# Switch-N-Sense.net
KiCad netlist of a schematic drawn in EAGLE
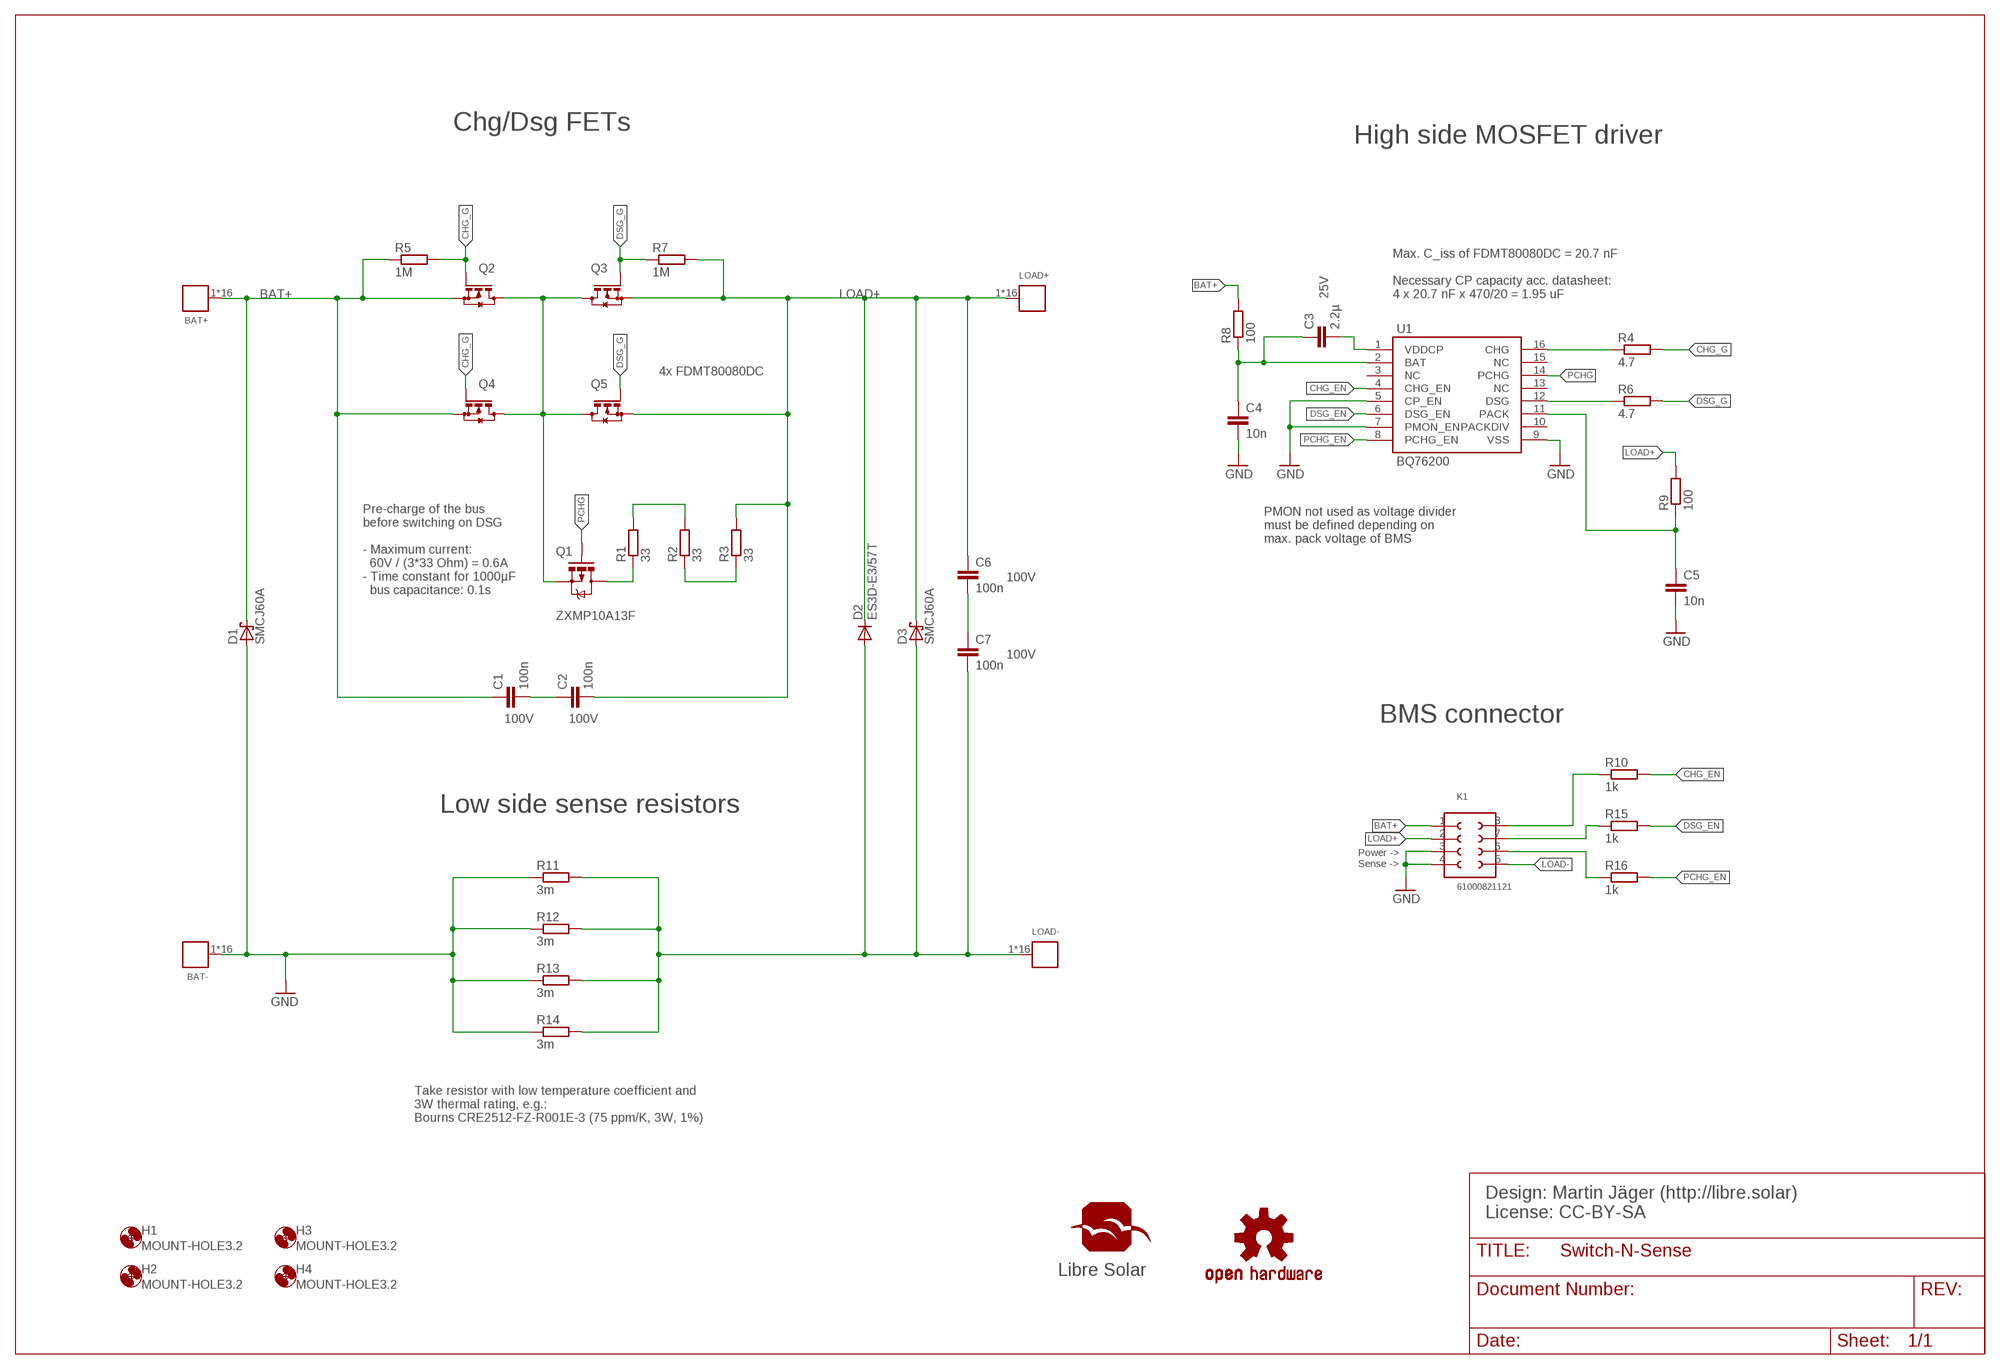
[diagram p0: schematic, sheet 1]

(export (version "E")
  (design (tool "Eeschema 10.0.6"))
  (components
    (comp (ref "BAT+")
      (value "WP-BUCF_G")
      (footprint "eagle-import:16PINS_CIR")
      (libsource (lib "eagle-import") (part "WP-BUCF_G"))
    )
    (comp (ref "BAT-")
      (value "WP-BUCF_G")
      (footprint "eagle-import:16PINS_CIR")
      (libsource (lib "eagle-import") (part "WP-BUCF_G"))
    )
    (comp (ref "C1")
      (value "100n")
      (footprint "eagle-import:C0603")
      (fields (field (name "MF") "WALSIN") (field (name "MPN") "0603B104K500CT"))
      (libsource (lib "eagle-import") (part "C-EUC0603"))
    )
    (comp (ref "C2")
      (value "100n")
      (footprint "eagle-import:C0603")
      (fields (field (name "MF") "WALSIN") (field (name "MPN") "0603B104K500CT"))
      (libsource (lib "eagle-import") (part "C-EUC0603"))
    )
    (comp (ref "C3")
      (value "2.2µ")
      (footprint "eagle-import:C0805")
      (fields (field (name "MF") "WALSIN") (field (name "MPN") "0603B104K500CT"))
      (libsource (lib "eagle-import") (part "C-EUC0805"))
    )
    (comp (ref "C4")
      (value "10n")
      (footprint "eagle-import:C0603")
      (fields (field (name "MF") "MURATA") (field (name "MPN") "GRM188R71H103KA01D."))
      (libsource (lib "eagle-import") (part "C-EUC0603"))
    )
    (comp (ref "C5")
      (value "10n")
      (footprint "eagle-import:C0603")
      (fields (field (name "MF") "MURATA") (field (name "MPN") "GRM188R71H103KA01D."))
      (libsource (lib "eagle-import") (part "C-EUC0603"))
    )
    (comp (ref "C6")
      (value "100n")
      (footprint "eagle-import:C0603")
      (fields (field (name "MF") "WALSIN") (field (name "MPN") "0603B104K500CT"))
      (libsource (lib "eagle-import") (part "C-EUC0603"))
    )
    (comp (ref "C7")
      (value "100n")
      (footprint "eagle-import:C0603")
      (fields (field (name "MF") "WALSIN") (field (name "MPN") "0603B104K500CT"))
      (libsource (lib "eagle-import") (part "C-EUC0603"))
    )
    (comp (ref "D1")
      (value "SMCJ60A")
      (footprint "eagle-import:SMC")
      (fields (field (name "MF") "FAIRCHILD SEMICONDUCTOR") (field (name "MPN") "SMCJ75A"))
      (libsource (lib "eagle-import") (part "SCHOTTKY-DIODESMC"))
    )
    (comp (ref "D2")
      (value "ES3D-E3/57T")
      (footprint "eagle-import:SMC")
      (fields (field (name "MF") "VISHAY") (field (name "MPN") "ES3D-E3/57T."))
      (libsource (lib "eagle-import") (part "DIODE-SMC"))
    )
    (comp (ref "D3")
      (value "SMCJ60A")
      (footprint "eagle-import:SMC")
      (fields (field (name "MF") "FAIRCHILD SEMICONDUCTOR") (field (name "MPN") "SMCJ75A"))
      (libsource (lib "eagle-import") (part "SCHOTTKY-DIODESMC"))
    )
    (comp (ref "H1")
      (value "MOUNT-HOLE3.2")
      (footprint "eagle-import:3,2")
      (libsource (lib "eagle-import") (part "MOUNT-HOLE3.2"))
    )
    (comp (ref "H2")
      (value "MOUNT-HOLE3.2")
      (footprint "eagle-import:3,2")
      (libsource (lib "eagle-import") (part "MOUNT-HOLE3.2"))
    )
    (comp (ref "H3")
      (value "MOUNT-HOLE3.2")
      (footprint "eagle-import:3,2")
      (libsource (lib "eagle-import") (part "MOUNT-HOLE3.2"))
    )
    (comp (ref "H4")
      (value "MOUNT-HOLE3.2")
      (footprint "eagle-import:3,2")
      (libsource (lib "eagle-import") (part "MOUNT-HOLE3.2"))
    )
    (comp (ref "K1")
      (value "61000821121")
      (footprint "eagle-import:61000821121")
      (libsource (lib "eagle-import") (part "61000821121"))
    )
    (comp (ref "LOAD+")
      (value "WP-BUCF_G")
      (footprint "eagle-import:16PINS_CIR")
      (libsource (lib "eagle-import") (part "WP-BUCF_G"))
    )
    (comp (ref "LOAD-")
      (value "WP-BUCF_G")
      (footprint "eagle-import:16PINS_CIR")
      (libsource (lib "eagle-import") (part "WP-BUCF_G"))
    )
    (comp (ref "N1")
      (value "OSHW-LOGOM")
      (footprint "eagle-import:OSHW-LOGO-M")
      (libsource (lib "eagle-import") (part "OSHW-LOGOM"))
    )
    (comp (ref "Q1")
      (value "ZXMP10A13F")
      (footprint "eagle-import:SOT23-3")
      (fields (field (name "MF") "DIODES INC.") (field (name "MPN") "ZXMP10A13FTA"))
      (libsource (lib "eagle-import") (part "MOSFET-PCHANNEL"))
    )
    (comp (ref "Q2")
      (value "FDMT80080DC")
      (footprint "eagle-import:FDMT80080DC")
      (libsource (lib "eagle-import") (part "FDMT80080DC"))
    )
    (comp (ref "Q3")
      (value "FDMT80080DC")
      (footprint "eagle-import:FDMT80080DC")
      (libsource (lib "eagle-import") (part "FDMT80080DC"))
    )
    (comp (ref "Q4")
      (value "FDMT80080DC")
      (footprint "eagle-import:FDMT80080DC")
      (libsource (lib "eagle-import") (part "FDMT80080DC"))
    )
    (comp (ref "Q5")
      (value "FDMT80080DC")
      (footprint "eagle-import:FDMT80080DC")
      (libsource (lib "eagle-import") (part "FDMT80080DC"))
    )
    (comp (ref "R1")
      (value "33")
      (footprint "eagle-import:R2010")
      (fields (field (name "MF") "WELWYN") (field (name "MPN") "ASC2010-33RFT4"))
      (libsource (lib "eagle-import") (part "R-EU_R2010"))
    )
    (comp (ref "R2")
      (value "33")
      (footprint "eagle-import:R2010")
      (fields (field (name "MF") "WELWYN") (field (name "MPN") "ASC2010-33RFT4"))
      (libsource (lib "eagle-import") (part "R-EU_R2010"))
    )
    (comp (ref "R3")
      (value "33")
      (footprint "eagle-import:R2010")
      (fields (field (name "MF") "WELWYN") (field (name "MPN") "ASC2010-33RFT4"))
      (libsource (lib "eagle-import") (part "R-EU_R2010"))
    )
    (comp (ref "R4")
      (value "4.7")
      (footprint "eagle-import:R0603")
      (fields (field (name "MF") "PANASONIC ELECTRONIC COMPONENTS") (field (name "MPN") "ERJU06F1004V"))
      (libsource (lib "eagle-import") (part "R-EU_R0603"))
    )
    (comp (ref "R5")
      (value "1M")
      (footprint "eagle-import:R0603")
      (fields (field (name "MF") "PANASONIC ELECTRONIC COMPONENTS") (field (name "MPN") "ERJU06F1004V"))
      (libsource (lib "eagle-import") (part "R-EU_R0603"))
    )
    (comp (ref "R6")
      (value "4.7")
      (footprint "eagle-import:R0603")
      (fields (field (name "MF") "PANASONIC ELECTRONIC COMPONENTS") (field (name "MPN") "ERJU06F1004V"))
      (libsource (lib "eagle-import") (part "R-EU_R0603"))
    )
    (comp (ref "R7")
      (value "1M")
      (footprint "eagle-import:R0603")
      (fields (field (name "MF") "PANASONIC ELECTRONIC COMPONENTS") (field (name "MPN") "ERJU06F1004V"))
      (libsource (lib "eagle-import") (part "R-EU_R0603"))
    )
    (comp (ref "R8")
      (value "100")
      (footprint "eagle-import:R0603")
      (fields (field (name "MF") "MULTICOMP") (field (name "MPN") "MCMR06X1001FTL"))
      (libsource (lib "eagle-import") (part "R-EU_R0603"))
    )
    (comp (ref "R9")
      (value "100")
      (footprint "eagle-import:R0603")
      (fields (field (name "MF") "MULTICOMP") (field (name "MPN") "MCMR06X1001FTL"))
      (libsource (lib "eagle-import") (part "R-EU_R0603"))
    )
    (comp (ref "R10")
      (value "1k")
      (footprint "eagle-import:R0603")
      (fields (field (name "MF") "PANASONIC ELECTRONIC COMPONENTS") (field (name "MPN") "ERJU06F1004V"))
      (libsource (lib "eagle-import") (part "R-EU_R0603"))
    )
    (comp (ref "R11")
      (value "3m")
      (footprint "eagle-import:R2512")
      (libsource (lib "eagle-import") (part "R-EU_R2512"))
    )
    (comp (ref "R12")
      (value "3m")
      (footprint "eagle-import:R2512")
      (libsource (lib "eagle-import") (part "R-EU_R2512"))
    )
    (comp (ref "R13")
      (value "3m")
      (footprint "eagle-import:R2512")
      (libsource (lib "eagle-import") (part "R-EU_R2512"))
    )
    (comp (ref "R14")
      (value "3m")
      (footprint "eagle-import:R2512")
      (libsource (lib "eagle-import") (part "R-EU_R2512"))
    )
    (comp (ref "R15")
      (value "1k")
      (footprint "eagle-import:R0603")
      (fields (field (name "MF") "PANASONIC ELECTRONIC COMPONENTS") (field (name "MPN") "ERJU06F1004V"))
      (libsource (lib "eagle-import") (part "R-EU_R0603"))
    )
    (comp (ref "R16")
      (value "1k")
      (footprint "eagle-import:R0603")
      (fields (field (name "MF") "PANASONIC ELECTRONIC COMPONENTS") (field (name "MPN") "ERJU06F1004V"))
      (libsource (lib "eagle-import") (part "R-EU_R0603"))
    )
    (comp (ref "U$1")
      (value "LIBRESOLAR_LOGO")
      (footprint "eagle-import:LIBRESOLAR_LOGO")
      (libsource (lib "eagle-import") (part "LIBRESOLAR_LOGO"))
    )
    (comp (ref "U1")
      (value "BQ76200")
      (footprint "eagle-import:TSSOP16")
      (libsource (lib "eagle-import") (part "BQ76200"))
    )
  )
  (nets
    (net (code "1") (name "BAT+") (class "Default")
      (node (ref "BAT+") (pin "1") (pinfunction "1_1") (pintype "passive"))
      (node (ref "BAT+") (pin "10") (pinfunction "1_10") (pintype "passive"))
      (node (ref "BAT+") (pin "11") (pinfunction "1_11") (pintype "passive"))
      (node (ref "BAT+") (pin "12") (pinfunction "1_12") (pintype "passive"))
      (node (ref "BAT+") (pin "13") (pinfunction "1_13") (pintype "passive"))
      (node (ref "BAT+") (pin "14") (pinfunction "1_14") (pintype "passive"))
      (node (ref "BAT+") (pin "15") (pinfunction "1_15") (pintype "passive"))
      (node (ref "BAT+") (pin "16") (pinfunction "1_16") (pintype "passive"))
      (node (ref "BAT+") (pin "2") (pinfunction "1_2") (pintype "passive"))
      (node (ref "BAT+") (pin "3") (pinfunction "1_3") (pintype "passive"))
      (node (ref "BAT+") (pin "4") (pinfunction "1_4") (pintype "passive"))
      (node (ref "BAT+") (pin "5") (pinfunction "1_5") (pintype "passive"))
      (node (ref "BAT+") (pin "6") (pinfunction "1_6") (pintype "passive"))
      (node (ref "BAT+") (pin "7") (pinfunction "1_7") (pintype "passive"))
      (node (ref "BAT+") (pin "8") (pinfunction "1_8") (pintype "passive"))
      (node (ref "BAT+") (pin "9") (pinfunction "1_9") (pintype "passive"))
      (node (ref "C1") (pin "1") (pinfunction "1_1") (pintype "passive"))
      (node (ref "D1") (pin "C") (pinfunction "C_C") (pintype "passive"))
      (node (ref "K1") (pin "1") (pinfunction "1_1") (pintype "passive"))
      (node (ref "Q2") (pin "S") (pinfunction "S_S") (pintype "passive"))
      (node (ref "Q4") (pin "S") (pinfunction "S_S") (pintype "passive"))
      (node (ref "R5") (pin "1") (pinfunction "1_1") (pintype "passive"))
      (node (ref "R8") (pin "2") (pinfunction "2_2") (pintype "passive"))
    )
    (net (code "2") (name "CHG_EN") (class "Default")
      (node (ref "R10") (pin "2") (pinfunction "2_2") (pintype "passive"))
      (node (ref "U1") (pin "4") (pinfunction "CHG_EN_4") (pintype "input"))
    )
    (net (code "3") (name "CHG_G") (class "Default")
      (node (ref "Q2") (pin "G") (pinfunction "G_G") (pintype "passive"))
      (node (ref "Q4") (pin "G") (pinfunction "G_G") (pintype "passive"))
      (node (ref "R4") (pin "2") (pinfunction "2_2") (pintype "passive"))
      (node (ref "R5") (pin "2") (pinfunction "2_2") (pintype "passive"))
    )
    (net (code "4") (name "DSG_EN") (class "Default")
      (node (ref "R15") (pin "2") (pinfunction "2_2") (pintype "passive"))
      (node (ref "U1") (pin "6") (pinfunction "DSG_EN_6") (pintype "input"))
    )
    (net (code "5") (name "DSG_G") (class "Default")
      (node (ref "Q3") (pin "G") (pinfunction "G_G") (pintype "passive"))
      (node (ref "Q5") (pin "G") (pinfunction "G_G") (pintype "passive"))
      (node (ref "R6") (pin "2") (pinfunction "2_2") (pintype "passive"))
      (node (ref "R7") (pin "1") (pinfunction "1_1") (pintype "passive"))
    )
    (net (code "6") (name "GND") (class "Default")
      (node (ref "BAT-") (pin "1") (pinfunction "1_1") (pintype "passive"))
      (node (ref "BAT-") (pin "10") (pinfunction "1_10") (pintype "passive"))
      (node (ref "BAT-") (pin "11") (pinfunction "1_11") (pintype "passive"))
      (node (ref "BAT-") (pin "12") (pinfunction "1_12") (pintype "passive"))
      (node (ref "BAT-") (pin "13") (pinfunction "1_13") (pintype "passive"))
      (node (ref "BAT-") (pin "14") (pinfunction "1_14") (pintype "passive"))
      (node (ref "BAT-") (pin "15") (pinfunction "1_15") (pintype "passive"))
      (node (ref "BAT-") (pin "16") (pinfunction "1_16") (pintype "passive"))
      (node (ref "BAT-") (pin "2") (pinfunction "1_2") (pintype "passive"))
      (node (ref "BAT-") (pin "3") (pinfunction "1_3") (pintype "passive"))
      (node (ref "BAT-") (pin "4") (pinfunction "1_4") (pintype "passive"))
      (node (ref "BAT-") (pin "5") (pinfunction "1_5") (pintype "passive"))
      (node (ref "BAT-") (pin "6") (pinfunction "1_6") (pintype "passive"))
      (node (ref "BAT-") (pin "7") (pinfunction "1_7") (pintype "passive"))
      (node (ref "BAT-") (pin "8") (pinfunction "1_8") (pintype "passive"))
      (node (ref "BAT-") (pin "9") (pinfunction "1_9") (pintype "passive"))
      (node (ref "C4") (pin "2") (pinfunction "2_2") (pintype "passive"))
      (node (ref "C5") (pin "2") (pinfunction "2_2") (pintype "passive"))
      (node (ref "D1") (pin "A") (pinfunction "A_A") (pintype "passive"))
      (node (ref "K1") (pin "3") (pinfunction "3_3") (pintype "passive"))
      (node (ref "K1") (pin "4") (pinfunction "4_4") (pintype "passive"))
      (node (ref "R11") (pin "1") (pinfunction "1_1") (pintype "passive"))
      (node (ref "R12") (pin "1") (pinfunction "1_1") (pintype "passive"))
      (node (ref "R13") (pin "1") (pinfunction "1_1") (pintype "passive"))
      (node (ref "R14") (pin "1") (pinfunction "1_1") (pintype "passive"))
      (node (ref "U1") (pin "5") (pinfunction "CP_EN_5") (pintype "input"))
      (node (ref "U1") (pin "7") (pinfunction "PMON_EN_7") (pintype "input"))
      (node (ref "U1") (pin "9") (pinfunction "VSS_9") (pintype "power_in"))
    )
    (net (code "7") (name "LOAD+") (class "Default")
      (node (ref "C2") (pin "2") (pinfunction "2_2") (pintype "passive"))
      (node (ref "C6") (pin "1") (pinfunction "1_1") (pintype "passive"))
      (node (ref "D2") (pin "C") (pinfunction "C_C") (pintype "passive"))
      (node (ref "D3") (pin "C") (pinfunction "C_C") (pintype "passive"))
      (node (ref "K1") (pin "2") (pinfunction "2_2") (pintype "passive"))
      (node (ref "LOAD+") (pin "1") (pinfunction "1_1") (pintype "passive"))
      (node (ref "LOAD+") (pin "10") (pinfunction "1_10") (pintype "passive"))
      (node (ref "LOAD+") (pin "11") (pinfunction "1_11") (pintype "passive"))
      (node (ref "LOAD+") (pin "12") (pinfunction "1_12") (pintype "passive"))
      (node (ref "LOAD+") (pin "13") (pinfunction "1_13") (pintype "passive"))
      (node (ref "LOAD+") (pin "14") (pinfunction "1_14") (pintype "passive"))
      (node (ref "LOAD+") (pin "15") (pinfunction "1_15") (pintype "passive"))
      (node (ref "LOAD+") (pin "16") (pinfunction "1_16") (pintype "passive"))
      (node (ref "LOAD+") (pin "2") (pinfunction "1_2") (pintype "passive"))
      (node (ref "LOAD+") (pin "3") (pinfunction "1_3") (pintype "passive"))
      (node (ref "LOAD+") (pin "4") (pinfunction "1_4") (pintype "passive"))
      (node (ref "LOAD+") (pin "5") (pinfunction "1_5") (pintype "passive"))
      (node (ref "LOAD+") (pin "6") (pinfunction "1_6") (pintype "passive"))
      (node (ref "LOAD+") (pin "7") (pinfunction "1_7") (pintype "passive"))
      (node (ref "LOAD+") (pin "8") (pinfunction "1_8") (pintype "passive"))
      (node (ref "LOAD+") (pin "9") (pinfunction "1_9") (pintype "passive"))
      (node (ref "Q3") (pin "S") (pinfunction "S_S") (pintype "passive"))
      (node (ref "Q5") (pin "S") (pinfunction "S_S") (pintype "passive"))
      (node (ref "R3") (pin "2") (pinfunction "2_2") (pintype "passive"))
      (node (ref "R7") (pin "2") (pinfunction "2_2") (pintype "passive"))
      (node (ref "R9") (pin "2") (pinfunction "2_2") (pintype "passive"))
    )
    (net (code "8") (name "LOAD-") (class "Default")
      (node (ref "C7") (pin "2") (pinfunction "2_2") (pintype "passive"))
      (node (ref "D2") (pin "A") (pinfunction "A_A") (pintype "passive"))
      (node (ref "D3") (pin "A") (pinfunction "A_A") (pintype "passive"))
      (node (ref "K1") (pin "5") (pinfunction "5_5") (pintype "passive"))
      (node (ref "LOAD-") (pin "1") (pinfunction "1_1") (pintype "passive"))
      (node (ref "LOAD-") (pin "10") (pinfunction "1_10") (pintype "passive"))
      (node (ref "LOAD-") (pin "11") (pinfunction "1_11") (pintype "passive"))
      (node (ref "LOAD-") (pin "12") (pinfunction "1_12") (pintype "passive"))
      (node (ref "LOAD-") (pin "13") (pinfunction "1_13") (pintype "passive"))
      (node (ref "LOAD-") (pin "14") (pinfunction "1_14") (pintype "passive"))
      (node (ref "LOAD-") (pin "15") (pinfunction "1_15") (pintype "passive"))
      (node (ref "LOAD-") (pin "16") (pinfunction "1_16") (pintype "passive"))
      (node (ref "LOAD-") (pin "2") (pinfunction "1_2") (pintype "passive"))
      (node (ref "LOAD-") (pin "3") (pinfunction "1_3") (pintype "passive"))
      (node (ref "LOAD-") (pin "4") (pinfunction "1_4") (pintype "passive"))
      (node (ref "LOAD-") (pin "5") (pinfunction "1_5") (pintype "passive"))
      (node (ref "LOAD-") (pin "6") (pinfunction "1_6") (pintype "passive"))
      (node (ref "LOAD-") (pin "7") (pinfunction "1_7") (pintype "passive"))
      (node (ref "LOAD-") (pin "8") (pinfunction "1_8") (pintype "passive"))
      (node (ref "LOAD-") (pin "9") (pinfunction "1_9") (pintype "passive"))
      (node (ref "R11") (pin "2") (pinfunction "2_2") (pintype "passive"))
      (node (ref "R12") (pin "2") (pinfunction "2_2") (pintype "passive"))
      (node (ref "R13") (pin "2") (pinfunction "2_2") (pintype "passive"))
      (node (ref "R14") (pin "2") (pinfunction "2_2") (pintype "passive"))
    )
    (net (code "9") (name "Net-(C1-Pad2)") (class "Default")
      (node (ref "C1") (pin "2") (pinfunction "2_2") (pintype "passive"))
      (node (ref "C2") (pin "1") (pinfunction "1_1") (pintype "passive"))
    )
    (net (code "10") (name "Net-(C6-Pad2)") (class "Default")
      (node (ref "C6") (pin "2") (pinfunction "2_2") (pintype "passive"))
      (node (ref "C7") (pin "1") (pinfunction "1_1") (pintype "passive"))
    )
    (net (code "11") (name "Net-(K1-Pad6)") (class "Default")
      (node (ref "K1") (pin "6") (pinfunction "6_6") (pintype "passive"))
      (node (ref "R16") (pin "1") (pinfunction "1_1") (pintype "passive"))
    )
    (net (code "12") (name "Net-(K1-Pad7)") (class "Default")
      (node (ref "K1") (pin "7") (pinfunction "7_7") (pintype "passive"))
      (node (ref "R15") (pin "1") (pinfunction "1_1") (pintype "passive"))
    )
    (net (code "13") (name "Net-(K1-Pad8)") (class "Default")
      (node (ref "K1") (pin "8") (pinfunction "8_8") (pintype "passive"))
      (node (ref "R10") (pin "1") (pinfunction "1_1") (pintype "passive"))
    )
    (net (code "14") (name "Net-(Q1-D)") (class "Default")
      (node (ref "Q1") (pin "3") (pinfunction "D_3") (pintype "passive"))
      (node (ref "R1") (pin "1") (pinfunction "1_1") (pintype "passive"))
    )
    (net (code "15") (name "Net-(Q1-S)") (class "Default")
      (node (ref "Q1") (pin "2") (pinfunction "S_2") (pintype "passive"))
      (node (ref "Q2") (pin "D") (pinfunction "D_D") (pintype "passive"))
      (node (ref "Q3") (pin "D") (pinfunction "D_D") (pintype "passive"))
      (node (ref "Q4") (pin "D") (pinfunction "D_D") (pintype "passive"))
      (node (ref "Q5") (pin "D") (pinfunction "D_D") (pintype "passive"))
    )
    (net (code "16") (name "Net-(R1-Pad2)") (class "Default")
      (node (ref "R1") (pin "2") (pinfunction "2_2") (pintype "passive"))
      (node (ref "R2") (pin "2") (pinfunction "2_2") (pintype "passive"))
    )
    (net (code "17") (name "Net-(R2-Pad1)") (class "Default")
      (node (ref "R2") (pin "1") (pinfunction "1_1") (pintype "passive"))
      (node (ref "R3") (pin "1") (pinfunction "1_1") (pintype "passive"))
    )
    (net (code "18") (name "Net-(U1-BAT)") (class "Default")
      (node (ref "C3") (pin "1") (pinfunction "1_1") (pintype "passive"))
      (node (ref "C4") (pin "1") (pinfunction "1_1") (pintype "passive"))
      (node (ref "R8") (pin "1") (pinfunction "1_1") (pintype "passive"))
      (node (ref "U1") (pin "2") (pinfunction "BAT_2") (pintype "power_in"))
    )
    (net (code "19") (name "Net-(U1-CHG)") (class "Default")
      (node (ref "R4") (pin "1") (pinfunction "1_1") (pintype "passive"))
      (node (ref "U1") (pin "16") (pinfunction "CHG_16") (pintype "output"))
    )
    (net (code "20") (name "Net-(U1-DSG)") (class "Default")
      (node (ref "R6") (pin "1") (pinfunction "1_1") (pintype "passive"))
      (node (ref "U1") (pin "12") (pinfunction "DSG_12") (pintype "output"))
    )
    (net (code "21") (name "Net-(U1-PACK)") (class "Default")
      (node (ref "C5") (pin "1") (pinfunction "1_1") (pintype "passive"))
      (node (ref "R9") (pin "1") (pinfunction "1_1") (pintype "passive"))
      (node (ref "U1") (pin "11") (pinfunction "PACK_11") (pintype "power_in"))
    )
    (net (code "22") (name "Net-(U1-VDDCP)") (class "Default")
      (node (ref "C3") (pin "2") (pinfunction "2_2") (pintype "passive"))
      (node (ref "U1") (pin "1") (pinfunction "VDDCP_1") (pintype "output"))
    )
    (net (code "23") (name "PCHG") (class "Default")
      (node (ref "Q1") (pin "1") (pinfunction "G_1") (pintype "passive"))
      (node (ref "U1") (pin "14") (pinfunction "PCHG_14") (pintype "output"))
    )
    (net (code "24") (name "PCHG_EN") (class "Default")
      (node (ref "R16") (pin "2") (pinfunction "2_2") (pintype "passive"))
      (node (ref "U1") (pin "8") (pinfunction "PCHG_EN_8") (pintype "input"))
    )
    (net (code "25") (name "unconnected-(U1-NC-Pad3)") (class "Default")
      (node (ref "U1") (pin "3") (pinfunction "NC_3") (pintype "no_connect"))
    )
    (net (code "26") (name "unconnected-(U1-NC-Pad13)") (class "Default")
      (node (ref "U1") (pin "13") (pinfunction "NC_13") (pintype "no_connect"))
    )
    (net (code "27") (name "unconnected-(U1-NC-Pad15)") (class "Default")
      (node (ref "U1") (pin "15") (pinfunction "NC_15") (pintype "no_connect"))
    )
    (net (code "28") (name "unconnected-(U1-PACKDIV-Pad10)") (class "Default")
      (node (ref "U1") (pin "10") (pinfunction "PACKDIV_10") (pintype "output"))
    )
  )
)
